# RP_AND_SAFETYSW.net
KiCad netlist of a schematic drawn in Altium Designer
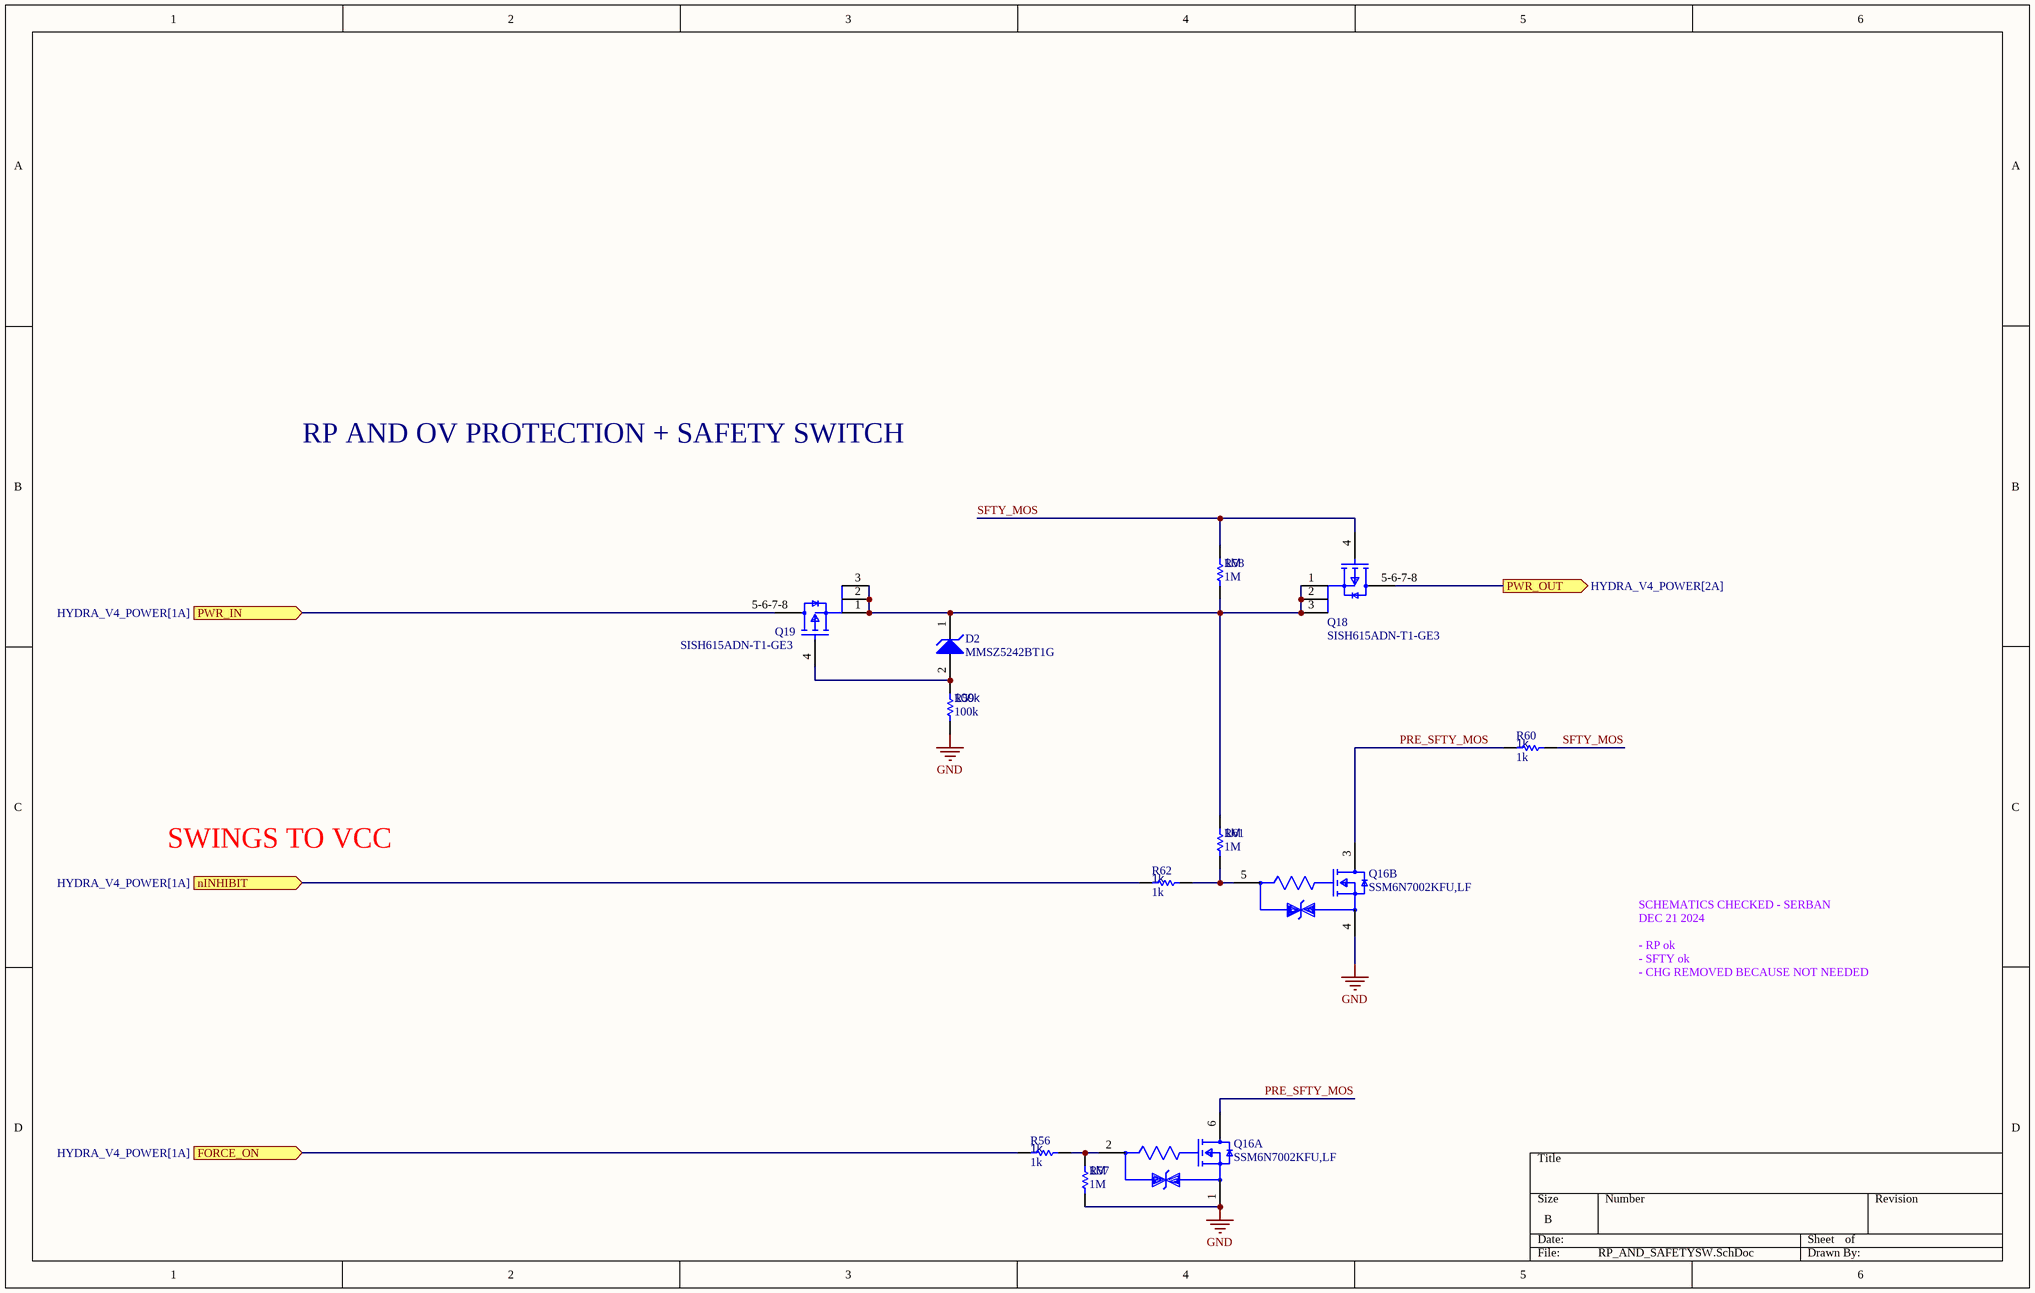
[diagram p0: RP_AND_SAFETYSW.SchDoc]

(export (version "E")
  (design (tool "Eeschema 10.0.6"))
  (components
    (comp (ref "D2")
      (value "MMSZ5242BT1G")
      (footprint "ONSC-SOD-123-2-425-04_V")
      (description "Zener Voltage Regulator, 500 mW, 2-Pin SOD-123, Pb-Free, Tape and Reel")
      (fields (field (name "MANUFACTURER") "On Semiconductor"))
      (libsource (lib "Altium Content Vault") (part "ONSC-K1A2-2"))
    )
    (comp (ref "Q16")
      (value "SSM6N7002KFU,LF")
      (footprint "FP-SSOP6-P-0_65A-MFG")
      (description "MOSFET 2N-CH 60V 0.3A")
      (libsource (lib "Altium Content Vault") (part "088aa6ac103fdeebe0d1c52ece6b7b9"))
    )
    (comp (ref "Q18")
      (value "SISH615ADN-T1-GE3")
      (footprint "SISH615ADN-T1-GE3-Footprint-1")
      (description "Trans MOSFET P-CH 20V 22.1A 8-Pin PowerPAK 1212 EP T/R")
      (libsource (lib "Space Concordia") (part "CMP-013-00036-4"))
    )
    (comp (ref "Q19")
      (value "SISH615ADN-T1-GE3")
      (footprint "SISH615ADN-T1-GE3-Footprint-1")
      (description "Trans MOSFET P-CH 20V 22.1A 8-Pin PowerPAK 1212 EP T/R")
      (libsource (lib "Space Concordia") (part "CMP-013-00036-4"))
    )
    (comp (ref "R56")
      (value "1k")
      (footprint "R0603B")
      (description "Resistor")
      (fields (field (name "ALTIUM_VALUE") "1k"))
      (libsource (lib "Space Concordia") (part "Resistor"))
    )
    (comp (ref "R57")
      (value "1M")
      (footprint "R0603B")
      (description "Resistor")
      (fields (field (name "ALTIUM_VALUE") "1M"))
      (libsource (lib "Space Concordia") (part "Resistor"))
    )
    (comp (ref "R58")
      (value "1M")
      (footprint "R0603B")
      (description "Resistor")
      (fields (field (name "ALTIUM_VALUE") "1M"))
      (libsource (lib "Space Concordia") (part "Resistor"))
    )
    (comp (ref "R59")
      (value "100k")
      (footprint "R0603B")
      (description "Resistor")
      (fields (field (name "ALTIUM_VALUE") "100k"))
      (libsource (lib "Space Concordia") (part "Resistor"))
    )
    (comp (ref "R60")
      (value "1k")
      (footprint "R0603B")
      (description "Resistor")
      (fields (field (name "ALTIUM_VALUE") "1k"))
      (libsource (lib "Space Concordia") (part "Resistor"))
    )
    (comp (ref "R61")
      (value "1M")
      (footprint "R0603B")
      (description "Resistor")
      (fields (field (name "ALTIUM_VALUE") "1M"))
      (libsource (lib "Space Concordia") (part "Resistor"))
    )
    (comp (ref "R62")
      (value "1k")
      (footprint "R0603B")
      (description "Resistor")
      (fields (field (name "ALTIUM_VALUE") "1k"))
      (libsource (lib "Space Concordia") (part "Resistor"))
    )
  )
  (nets
    (net (code "1") (name "/FORCE_ON") (class "Default")
      (node (ref "R56") (pin "2") (pinfunction "2_2") (pintype "passive"))
    )
    (net (code "2") (name "/PRE_SFTY_MOS") (class "Default")
      (node (ref "Q16") (pin "3") (pinfunction "Drain2_3") (pintype "passive"))
      (node (ref "Q16") (pin "6") (pinfunction "Drain1_6") (pintype "passive"))
      (node (ref "R60") (pin "2") (pinfunction "2_2") (pintype "passive"))
    )
    (net (code "3") (name "/PWR_IN") (class "Default")
      (node (ref "Q19") (pin "5-6-7-8") (pinfunction "D_5-6-7-8") (pintype "passive"))
    )
    (net (code "4") (name "/PWR_OUT") (class "Default")
      (node (ref "Q18") (pin "5-6-7-8") (pinfunction "D_5-6-7-8") (pintype "passive"))
    )
    (net (code "5") (name "/SFTY_MOS") (class "Default")
      (node (ref "Q18") (pin "4") (pinfunction "G_4") (pintype "passive"))
      (node (ref "R58") (pin "2") (pinfunction "2_2") (pintype "passive"))
      (node (ref "R60") (pin "1") (pinfunction "1_1") (pintype "passive"))
    )
    (net (code "6") (name "/nINHIBIT") (class "Default")
      (node (ref "R62") (pin "2") (pinfunction "2_2") (pintype "passive"))
    )
    (net (code "7") (name "GND") (class "Default")
      (node (ref "Q16") (pin "1") (pinfunction "Source1_1") (pintype "passive"))
      (node (ref "Q16") (pin "4") (pinfunction "Source2_4") (pintype "passive"))
      (node (ref "R57") (pin "2") (pinfunction "2_2") (pintype "passive"))
      (node (ref "R59") (pin "1") (pinfunction "1_1") (pintype "passive"))
    )
    (net (code "8") (name "Net-(D2-A)") (class "Default")
      (node (ref "D2") (pin "2") (pinfunction "A_2") (pintype "passive"))
      (node (ref "Q19") (pin "4") (pinfunction "G_4") (pintype "passive"))
      (node (ref "R59") (pin "2") (pinfunction "2_2") (pintype "passive"))
    )
    (net (code "9") (name "Net-(D2-K)") (class "Default")
      (node (ref "D2") (pin "1") (pinfunction "K_1") (pintype "passive"))
      (node (ref "Q18") (pin "1") (pinfunction "S_1") (pintype "passive"))
      (node (ref "Q18") (pin "2") (pinfunction "S_2") (pintype "passive"))
      (node (ref "Q18") (pin "3") (pinfunction "S_3") (pintype "passive"))
      (node (ref "Q19") (pin "1") (pinfunction "S_1") (pintype "passive"))
      (node (ref "Q19") (pin "2") (pinfunction "S_2") (pintype "passive"))
      (node (ref "Q19") (pin "3") (pinfunction "S_3") (pintype "passive"))
      (node (ref "R58") (pin "1") (pinfunction "1_1") (pintype "passive"))
      (node (ref "R61") (pin "1") (pinfunction "1_1") (pintype "passive"))
    )
    (net (code "10") (name "Net-(Q16A-Gate1)") (class "Default")
      (node (ref "Q16") (pin "2") (pinfunction "Gate1_2") (pintype "passive"))
      (node (ref "R56") (pin "1") (pinfunction "1_1") (pintype "passive"))
      (node (ref "R57") (pin "1") (pinfunction "1_1") (pintype "passive"))
    )
    (net (code "11") (name "Net-(Q16B-Gate2)") (class "Default")
      (node (ref "Q16") (pin "5") (pinfunction "Gate2_5") (pintype "passive"))
      (node (ref "R61") (pin "2") (pinfunction "2_2") (pintype "passive"))
      (node (ref "R62") (pin "1") (pinfunction "1_1") (pintype "passive"))
    )
  )
)
